# 3V3_Regulator.net
KiCad netlist of a schematic drawn in Altium Designer
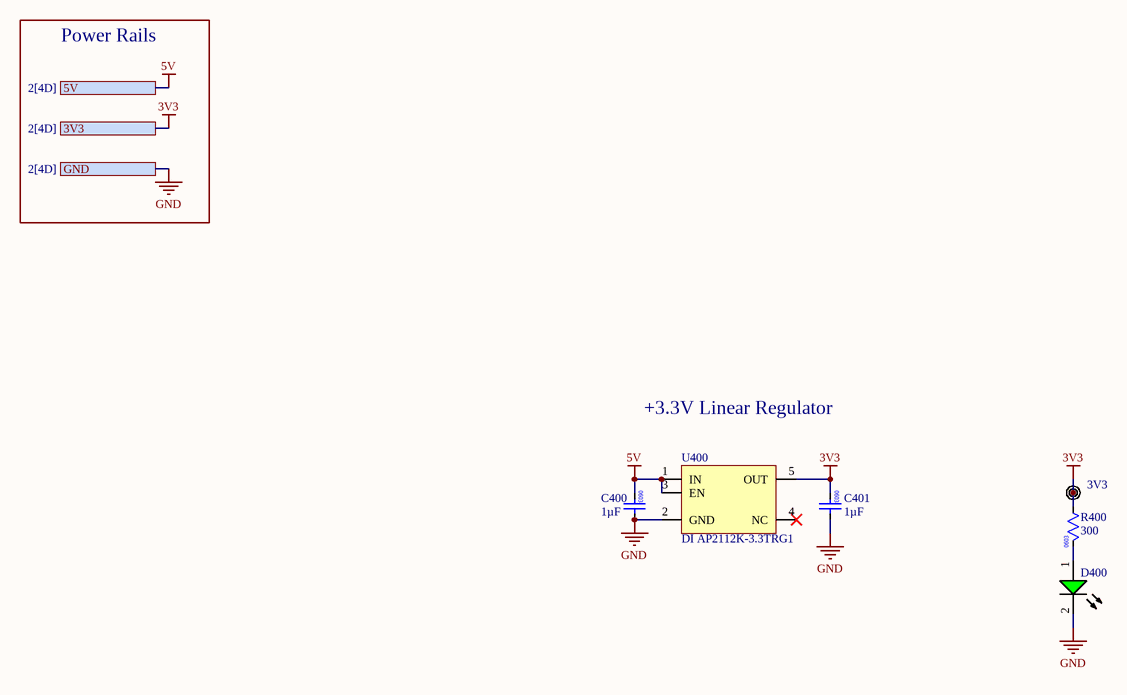
[diagram p0: 3V3_Regulator.SchDoc]

(export (version "E")
  (design (tool "Eeschema 10.0.6"))
  (components
    (comp (ref "C400")
      (value "1µF")
      (footprint "0603 Capacitor Footprint")
      (description "CAP CER 1UF 25V X7R 0603")
      (fields
        (field (name "MANUFACTURER PART NUMBER") "GCM188R71E105KA64J")
        (field (name "DIGIKEY PART NUMBER") "490-GCM188R71E105KA64JCT-ND")
      )
      (libsource (lib "UBC Formula Electric") (part "0603 Generic Ceramic Capacitor"))
    )
    (comp (ref "C401")
      (value "1µF")
      (footprint "0603 Capacitor Footprint")
      (description "CAP CER 1UF 25V X7R 0603")
      (fields
        (field (name "MANUFACTURER PART NUMBER") "GCM188R71E105KA64J")
        (field (name "DIGIKEY PART NUMBER") "490-GCM188R71E105KA64JCT-ND")
      )
      (libsource (lib "UBC Formula Electric") (part "0603 Generic Ceramic Capacitor"))
    )
    (comp (ref "D400")
      (value "Lite-On LTST-C193KGKT-5A")
      (footprint "Lite-On LTST-C193KGKT-5A GREEN (1608)")
      (description "LED GREEN CLEAR CHIP SMD")
      (fields (field (name "SOURCE") "UBC Formula Electric.SchLib"))
      (libsource (lib "UBC Formula Electric") (part "Lite-On LTST-C193KGKT-5A"))
    )
    (comp (ref "R400")
      (value "300")
      (footprint "0603 Resistor Footprint")
      (description "RES SMD 300 OHM 1% 1/3W 0603")
      (fields (field (name "TOLERANCE") "1%") (field (name "POWER") "250mW"))
      (libsource (lib "UBC Formula Electric") (part "RES-2"))
    )
    (comp (ref "TP400")
      (value "3V3")
      (footprint "TESTPOINT")
      (fields (field (name "SOURCE") "UBC Formula Electric.SchLib"))
      (libsource (lib "UBC Formula Electric") (part "Thru-Hole Test Point"))
    )
    (comp (ref "U400")
      (value "DI AP2112K-3.3TRG1")
      (footprint "DI AP2112K-3.3TRG1")
      (description "Linear Voltage Regulator IC Positive Fixed 1 Output  600mA SOT-25")
      (fields (field (name "SOURCE") "Quad_Inverter.SchLib"))
      (libsource (lib "UBC Formula Electric") (part "DI AP2112K-3.3TRG1"))
    )
  )
  (nets
    (net (code "1") (name "3V3") (class "Default")
      (node (ref "C401") (pin "2") (pinfunction "2_2") (pintype "passive"))
      (node (ref "R400") (pin "1") (pinfunction "1_1") (pintype "passive"))
      (node (ref "TP400") (pin "1") (pinfunction "TP_1") (pintype "passive"))
      (node (ref "U400") (pin "5") (pinfunction "OUT_5") (pintype "power_in"))
    )
    (net (code "2") (name "5V") (class "Default")
      (node (ref "C400") (pin "2") (pinfunction "2_2") (pintype "passive"))
      (node (ref "U400") (pin "1") (pinfunction "IN_1") (pintype "power_in"))
      (node (ref "U400") (pin "3") (pinfunction "EN_3") (pintype "passive"))
    )
    (net (code "3") (name "GND") (class "Default")
      (node (ref "C400") (pin "1") (pinfunction "1_1") (pintype "passive"))
      (node (ref "C401") (pin "1") (pinfunction "1_1") (pintype "passive"))
      (node (ref "D400") (pin "2") (pinfunction "K_2") (pintype "passive"))
      (node (ref "U400") (pin "2") (pinfunction "GND_2") (pintype "power_in"))
    )
    (net (code "4") (name "Net-(D400-A)") (class "Default")
      (node (ref "D400") (pin "1") (pinfunction "A_1") (pintype "passive"))
      (node (ref "R400") (pin "2") (pinfunction "2_2") (pintype "passive"))
    )
    (net (code "5") (name "unconnected-(U400-NC-Pad4)") (class "Default")
      (node (ref "U400") (pin "4") (pinfunction "NC_4") (pintype "passive+no_connect"))
    )
  )
)
